# GEM_AVD_eFuse.net
KiCad netlist of a schematic drawn in Altium Designer
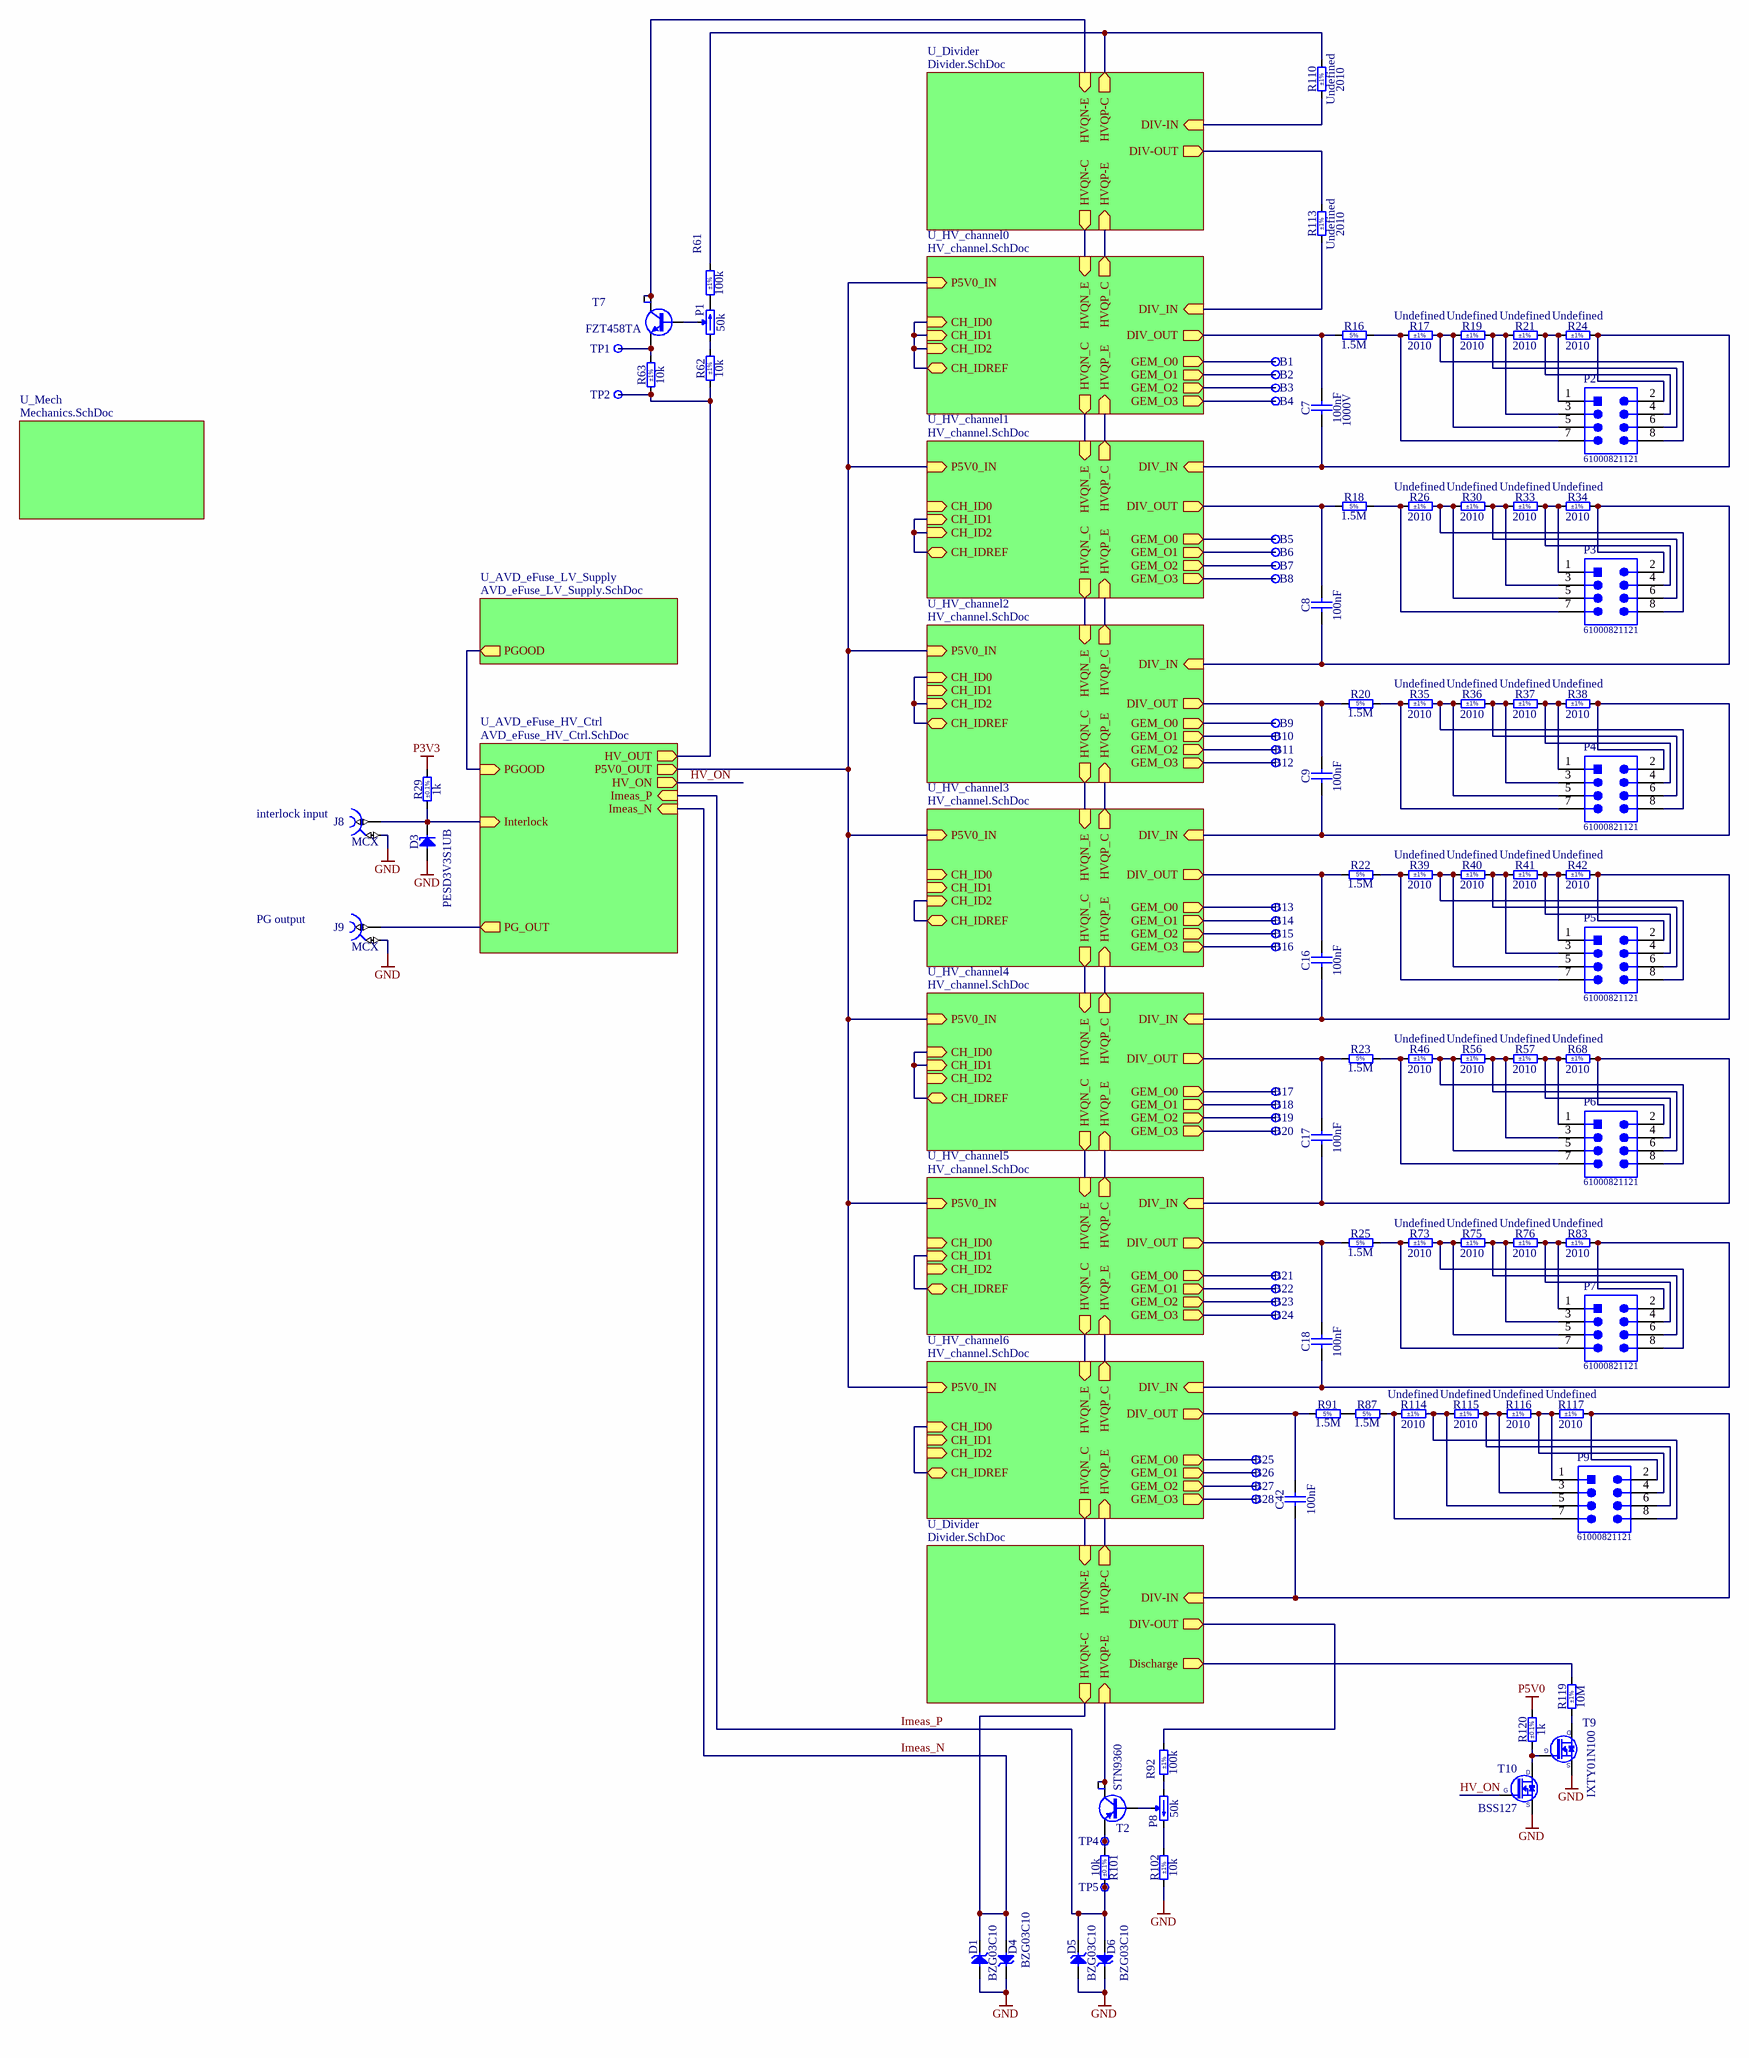
[diagram p0: GEM_AVD_eFuse.SchDoc]

(export (version "E")
  (design (tool "Eeschema 10.0.6"))
  (components
    (comp (ref "B1")
      (value "Socket")
      (footprint "MULTI-CONTACT_23.1000")
      (description "Single Terminal Socket")
      (fields
        (field (name "PART NUMBER") "MULTI-CONTACT_23.1000")
        (field (name "MANUFACTURER") "MULTI-CONTACT")
        (field (name "AUTHOR") "CERN DEM JLC")
      )
      (libsource (lib "Connectors") (part "Single Terminal Socket"))
    )
    (comp (ref "B2")
      (value "Socket")
      (footprint "MULTI-CONTACT_23.1000")
      (description "Single Terminal Socket")
      (fields
        (field (name "PART NUMBER") "MULTI-CONTACT_23.1000")
        (field (name "MANUFACTURER") "MULTI-CONTACT")
        (field (name "AUTHOR") "CERN DEM JLC")
      )
      (libsource (lib "Connectors") (part "Single Terminal Socket"))
    )
    (comp (ref "B3")
      (value "Socket")
      (footprint "MULTI-CONTACT_23.1000")
      (description "Single Terminal Socket")
      (fields
        (field (name "PART NUMBER") "MULTI-CONTACT_23.1000")
        (field (name "MANUFACTURER") "MULTI-CONTACT")
        (field (name "AUTHOR") "CERN DEM JLC")
      )
      (libsource (lib "Connectors") (part "Single Terminal Socket"))
    )
    (comp (ref "B4")
      (value "Socket")
      (footprint "MULTI-CONTACT_23.1000")
      (description "Single Terminal Socket")
      (fields
        (field (name "PART NUMBER") "MULTI-CONTACT_23.1000")
        (field (name "MANUFACTURER") "MULTI-CONTACT")
        (field (name "AUTHOR") "CERN DEM JLC")
      )
      (libsource (lib "Connectors") (part "Single Terminal Socket"))
    )
    (comp (ref "B5")
      (value "Socket")
      (footprint "MULTI-CONTACT_23.1000")
      (description "Single Terminal Socket")
      (fields
        (field (name "PART NUMBER") "MULTI-CONTACT_23.1000")
        (field (name "MANUFACTURER") "MULTI-CONTACT")
        (field (name "AUTHOR") "CERN DEM JLC")
      )
      (libsource (lib "Connectors") (part "Single Terminal Socket"))
    )
    (comp (ref "B6")
      (value "Socket")
      (footprint "MULTI-CONTACT_23.1000")
      (description "Single Terminal Socket")
      (fields
        (field (name "PART NUMBER") "MULTI-CONTACT_23.1000")
        (field (name "MANUFACTURER") "MULTI-CONTACT")
        (field (name "AUTHOR") "CERN DEM JLC")
      )
      (libsource (lib "Connectors") (part "Single Terminal Socket"))
    )
    (comp (ref "B7")
      (value "Socket")
      (footprint "MULTI-CONTACT_23.1000")
      (description "Single Terminal Socket")
      (fields
        (field (name "PART NUMBER") "MULTI-CONTACT_23.1000")
        (field (name "MANUFACTURER") "MULTI-CONTACT")
        (field (name "AUTHOR") "CERN DEM JLC")
      )
      (libsource (lib "Connectors") (part "Single Terminal Socket"))
    )
    (comp (ref "B8")
      (value "Socket")
      (footprint "MULTI-CONTACT_23.1000")
      (description "Single Terminal Socket")
      (fields
        (field (name "PART NUMBER") "MULTI-CONTACT_23.1000")
        (field (name "MANUFACTURER") "MULTI-CONTACT")
        (field (name "AUTHOR") "CERN DEM JLC")
      )
      (libsource (lib "Connectors") (part "Single Terminal Socket"))
    )
    (comp (ref "B9")
      (value "Socket")
      (footprint "MULTI-CONTACT_23.1000")
      (description "Single Terminal Socket")
      (fields
        (field (name "PART NUMBER") "MULTI-CONTACT_23.1000")
        (field (name "MANUFACTURER") "MULTI-CONTACT")
        (field (name "AUTHOR") "CERN DEM JLC")
      )
      (libsource (lib "Connectors") (part "Single Terminal Socket"))
    )
    (comp (ref "B10")
      (value "Socket")
      (footprint "MULTI-CONTACT_23.1000")
      (description "Single Terminal Socket")
      (fields
        (field (name "PART NUMBER") "MULTI-CONTACT_23.1000")
        (field (name "MANUFACTURER") "MULTI-CONTACT")
        (field (name "AUTHOR") "CERN DEM JLC")
      )
      (libsource (lib "Connectors") (part "Single Terminal Socket"))
    )
    (comp (ref "B11")
      (value "Socket")
      (footprint "MULTI-CONTACT_23.1000")
      (description "Single Terminal Socket")
      (fields
        (field (name "PART NUMBER") "MULTI-CONTACT_23.1000")
        (field (name "MANUFACTURER") "MULTI-CONTACT")
        (field (name "AUTHOR") "CERN DEM JLC")
      )
      (libsource (lib "Connectors") (part "Single Terminal Socket"))
    )
    (comp (ref "B12")
      (value "Socket")
      (footprint "MULTI-CONTACT_23.1000")
      (description "Single Terminal Socket")
      (fields
        (field (name "PART NUMBER") "MULTI-CONTACT_23.1000")
        (field (name "MANUFACTURER") "MULTI-CONTACT")
        (field (name "AUTHOR") "CERN DEM JLC")
      )
      (libsource (lib "Connectors") (part "Single Terminal Socket"))
    )
    (comp (ref "B13")
      (value "Socket")
      (footprint "MULTI-CONTACT_23.1000")
      (description "Single Terminal Socket")
      (fields
        (field (name "PART NUMBER") "MULTI-CONTACT_23.1000")
        (field (name "MANUFACTURER") "MULTI-CONTACT")
        (field (name "AUTHOR") "CERN DEM JLC")
      )
      (libsource (lib "Connectors") (part "Single Terminal Socket"))
    )
    (comp (ref "B14")
      (value "Socket")
      (footprint "MULTI-CONTACT_23.1000")
      (description "Single Terminal Socket")
      (fields
        (field (name "PART NUMBER") "MULTI-CONTACT_23.1000")
        (field (name "MANUFACTURER") "MULTI-CONTACT")
        (field (name "AUTHOR") "CERN DEM JLC")
      )
      (libsource (lib "Connectors") (part "Single Terminal Socket"))
    )
    (comp (ref "B15")
      (value "Socket")
      (footprint "MULTI-CONTACT_23.1000")
      (description "Single Terminal Socket")
      (fields
        (field (name "PART NUMBER") "MULTI-CONTACT_23.1000")
        (field (name "MANUFACTURER") "MULTI-CONTACT")
        (field (name "AUTHOR") "CERN DEM JLC")
      )
      (libsource (lib "Connectors") (part "Single Terminal Socket"))
    )
    (comp (ref "B16")
      (value "Socket")
      (footprint "MULTI-CONTACT_23.1000")
      (description "Single Terminal Socket")
      (fields
        (field (name "PART NUMBER") "MULTI-CONTACT_23.1000")
        (field (name "MANUFACTURER") "MULTI-CONTACT")
        (field (name "AUTHOR") "CERN DEM JLC")
      )
      (libsource (lib "Connectors") (part "Single Terminal Socket"))
    )
    (comp (ref "B17")
      (value "Socket")
      (footprint "MULTI-CONTACT_23.1000")
      (description "Single Terminal Socket")
      (fields
        (field (name "PART NUMBER") "MULTI-CONTACT_23.1000")
        (field (name "MANUFACTURER") "MULTI-CONTACT")
        (field (name "AUTHOR") "CERN DEM JLC")
      )
      (libsource (lib "Connectors") (part "Single Terminal Socket"))
    )
    (comp (ref "B18")
      (value "Socket")
      (footprint "MULTI-CONTACT_23.1000")
      (description "Single Terminal Socket")
      (fields
        (field (name "PART NUMBER") "MULTI-CONTACT_23.1000")
        (field (name "MANUFACTURER") "MULTI-CONTACT")
        (field (name "AUTHOR") "CERN DEM JLC")
      )
      (libsource (lib "Connectors") (part "Single Terminal Socket"))
    )
    (comp (ref "B19")
      (value "Socket")
      (footprint "MULTI-CONTACT_23.1000")
      (description "Single Terminal Socket")
      (fields
        (field (name "PART NUMBER") "MULTI-CONTACT_23.1000")
        (field (name "MANUFACTURER") "MULTI-CONTACT")
        (field (name "AUTHOR") "CERN DEM JLC")
      )
      (libsource (lib "Connectors") (part "Single Terminal Socket"))
    )
    (comp (ref "B20")
      (value "Socket")
      (footprint "MULTI-CONTACT_23.1000")
      (description "Single Terminal Socket")
      (fields
        (field (name "PART NUMBER") "MULTI-CONTACT_23.1000")
        (field (name "MANUFACTURER") "MULTI-CONTACT")
        (field (name "AUTHOR") "CERN DEM JLC")
      )
      (libsource (lib "Connectors") (part "Single Terminal Socket"))
    )
    (comp (ref "B21")
      (value "Socket")
      (footprint "MULTI-CONTACT_23.1000")
      (description "Single Terminal Socket")
      (fields
        (field (name "PART NUMBER") "MULTI-CONTACT_23.1000")
        (field (name "MANUFACTURER") "MULTI-CONTACT")
        (field (name "AUTHOR") "CERN DEM JLC")
      )
      (libsource (lib "Connectors") (part "Single Terminal Socket"))
    )
    (comp (ref "B22")
      (value "Socket")
      (footprint "MULTI-CONTACT_23.1000")
      (description "Single Terminal Socket")
      (fields
        (field (name "PART NUMBER") "MULTI-CONTACT_23.1000")
        (field (name "MANUFACTURER") "MULTI-CONTACT")
        (field (name "AUTHOR") "CERN DEM JLC")
      )
      (libsource (lib "Connectors") (part "Single Terminal Socket"))
    )
    (comp (ref "B23")
      (value "Socket")
      (footprint "MULTI-CONTACT_23.1000")
      (description "Single Terminal Socket")
      (fields
        (field (name "PART NUMBER") "MULTI-CONTACT_23.1000")
        (field (name "MANUFACTURER") "MULTI-CONTACT")
        (field (name "AUTHOR") "CERN DEM JLC")
      )
      (libsource (lib "Connectors") (part "Single Terminal Socket"))
    )
    (comp (ref "B24")
      (value "Socket")
      (footprint "MULTI-CONTACT_23.1000")
      (description "Single Terminal Socket")
      (fields
        (field (name "PART NUMBER") "MULTI-CONTACT_23.1000")
        (field (name "MANUFACTURER") "MULTI-CONTACT")
        (field (name "AUTHOR") "CERN DEM JLC")
      )
      (libsource (lib "Connectors") (part "Single Terminal Socket"))
    )
    (comp (ref "B25")
      (value "Socket")
      (footprint "MULTI-CONTACT_23.1000")
      (description "Single Terminal Socket")
      (fields
        (field (name "PART NUMBER") "MULTI-CONTACT_23.1000")
        (field (name "MANUFACTURER") "MULTI-CONTACT")
        (field (name "AUTHOR") "CERN DEM JLC")
      )
      (libsource (lib "Connectors") (part "Single Terminal Socket"))
    )
    (comp (ref "B26")
      (value "Socket")
      (footprint "MULTI-CONTACT_23.1000")
      (description "Single Terminal Socket")
      (fields
        (field (name "PART NUMBER") "MULTI-CONTACT_23.1000")
        (field (name "MANUFACTURER") "MULTI-CONTACT")
        (field (name "AUTHOR") "CERN DEM JLC")
      )
      (libsource (lib "Connectors") (part "Single Terminal Socket"))
    )
    (comp (ref "B27")
      (value "Socket")
      (footprint "MULTI-CONTACT_23.1000")
      (description "Single Terminal Socket")
      (fields
        (field (name "PART NUMBER") "MULTI-CONTACT_23.1000")
        (field (name "MANUFACTURER") "MULTI-CONTACT")
        (field (name "AUTHOR") "CERN DEM JLC")
      )
      (libsource (lib "Connectors") (part "Single Terminal Socket"))
    )
    (comp (ref "B28")
      (value "Socket")
      (footprint "MULTI-CONTACT_23.1000")
      (description "Single Terminal Socket")
      (fields
        (field (name "PART NUMBER") "MULTI-CONTACT_23.1000")
        (field (name "MANUFACTURER") "MULTI-CONTACT")
        (field (name "AUTHOR") "CERN DEM JLC")
      )
      (libsource (lib "Connectors") (part "Single Terminal Socket"))
    )
    (comp (ref "C7")
      (value "100nF")
      (footprint "CAPC4532X185N")
      (description "Non-polarised capacitor")
      (fields
        (field (name "PART NUMBER") "CC1812_100NF_1000V_10%_X7R_KEMET_HV FT-CAP")
        (field (name "VOLTAGE") "1000V")
        (field (name "TOLERANCE") "±10%")
        (field (name "AUTHOR") "CERN DEM MR")
      )
      (libsource (lib "Capacitors") (part "Capacitor - non polarized"))
    )
    (comp (ref "C8")
      (value "100nF")
      (footprint "CAPC4532X185N")
      (description "Non-polarised capacitor")
      (fields
        (field (name "PART NUMBER") "CC1812_100NF_1000V_10%_X7R_KEMET_HV FT-CAP")
        (field (name "VOLTAGE") "1000V")
        (field (name "AUTHOR") "CERN DEM MR")
      )
      (libsource (lib "Capacitors") (part "Capacitor - non polarized"))
    )
    (comp (ref "C9")
      (value "100nF")
      (footprint "CAPC4532X185N")
      (description "Non-polarised capacitor")
      (fields
        (field (name "PART NUMBER") "CC1812_100NF_1000V_10%_X7R_KEMET_HV FT-CAP")
        (field (name "VOLTAGE") "1000V")
        (field (name "AUTHOR") "CERN DEM MR")
      )
      (libsource (lib "Capacitors") (part "Capacitor - non polarized"))
    )
    (comp (ref "C16")
      (value "100nF")
      (footprint "CAPC4532X185N")
      (description "Non-polarised capacitor")
      (fields
        (field (name "PART NUMBER") "CC1812_100NF_1000V_10%_X7R_KEMET_HV FT-CAP")
        (field (name "VOLTAGE") "1000V")
        (field (name "AUTHOR") "CERN DEM MR")
      )
      (libsource (lib "Capacitors") (part "Capacitor - non polarized"))
    )
    (comp (ref "C17")
      (value "100nF")
      (footprint "CAPC4532X185N")
      (description "Non-polarised capacitor")
      (fields
        (field (name "PART NUMBER") "CC1812_100NF_1000V_10%_X7R_KEMET_HV FT-CAP")
        (field (name "VOLTAGE") "1000V")
        (field (name "AUTHOR") "CERN DEM MR")
      )
      (libsource (lib "Capacitors") (part "Capacitor - non polarized"))
    )
    (comp (ref "C18")
      (value "100nF")
      (footprint "CAPC4532X185N")
      (description "Non-polarised capacitor")
      (fields
        (field (name "PART NUMBER") "CC1812_100NF_1000V_10%_X7R_KEMET_HV FT-CAP")
        (field (name "VOLTAGE") "1000V")
        (field (name "AUTHOR") "CERN DEM MR")
      )
      (libsource (lib "Capacitors") (part "Capacitor - non polarized"))
    )
    (comp (ref "C42")
      (value "100nF")
      (footprint "CAPC4532X185N")
      (description "Non-polarised capacitor")
      (fields
        (field (name "PART NUMBER") "CC1812_100NF_1000V_10%_X7R_KEMET_HV FT-CAP")
        (field (name "VOLTAGE") "1000V")
        (field (name "AUTHOR") "CERN DEM MR")
      )
      (libsource (lib "Capacitors") (part "Capacitor - non polarized"))
    )
    (comp (ref "D1")
      (value "BZG03C10")
      (footprint "DIOM5326X230N")
      (description "Zener Diode")
      (fields
        (field (name "VOLTAGE") "10V")
        (field (name "POWER") "1.25W")
        (field (name "AUTHOR") "CERN DEM JLC")
      )
      (libsource (lib "ICs And Semiconductors") (part "Diode Zener"))
    )
    (comp (ref "D3")
      (value "PESD3V3S1UB")
      (footprint "SODFL1608X65N")
      (description "ESD protection diode")
      (fields
        (field (name "VOLTAGE") "3V3")
        (field (name "POWER") "330W")
        (field (name "AUTHOR") "CERN DEM JLC")
      )
      (libsource (lib "ICs And Semiconductors") (part "Diode ESD"))
    )
    (comp (ref "D4")
      (value "BZG03C10")
      (footprint "DIOM5326X230N")
      (description "Zener Diode")
      (fields
        (field (name "VOLTAGE") "10V")
        (field (name "POWER") "1.25W")
        (field (name "AUTHOR") "CERN DEM JLC")
      )
      (libsource (lib "ICs And Semiconductors") (part "Diode Zener"))
    )
    (comp (ref "D5")
      (value "BZG03C10")
      (footprint "DIOM5326X230N")
      (description "Zener Diode")
      (fields
        (field (name "VOLTAGE") "10V")
        (field (name "POWER") "1.25W")
        (field (name "AUTHOR") "CERN DEM JLC")
      )
      (libsource (lib "ICs And Semiconductors") (part "Diode Zener"))
    )
    (comp (ref "D6")
      (value "BZG03C10")
      (footprint "DIOM5326X230N")
      (description "Zener Diode")
      (fields
        (field (name "VOLTAGE") "10V")
        (field (name "POWER") "1.25W")
        (field (name "AUTHOR") "CERN DEM JLC")
      )
      (libsource (lib "ICs And Semiconductors") (part "Diode Zener"))
    )
    (comp (ref "J8")
      (value "MCX")
      (footprint "AMPHENOL_919-383J-51A")
      (fields
        (field (name "PART NUMBER") "AMPHENOL_919-383J-51A")
        (field (name "MANUFACTURER") "AMPHENOL")
        (field (name "MANUFACTURER PART NUMBER") "919-383J-51A")
        (field (name "AUTHOR") "CERN DEM BC")
      )
      (libsource (lib "Connectors") (part "Coax_1Female_1Shield"))
    )
    (comp (ref "J9")
      (value "MCX")
      (footprint "AMPHENOL_919-383J-51A")
      (fields
        (field (name "PART NUMBER") "AMPHENOL_919-383J-51A")
        (field (name "MANUFACTURER") "AMPHENOL")
        (field (name "MANUFACTURER PART NUMBER") "919-383J-51A")
        (field (name "AUTHOR") "CERN DEM BC")
      )
      (libsource (lib "Connectors") (part "Coax_1Female_1Shield"))
    )
    (comp (ref "P1")
      (value "50k")
      (footprint "TRIM_BOURNS_3266W")
      (description "Trimming Potentiometer")
      (fields
        (field (name "PART NUMBER") "TRIM_12T_50K_BOURNS_3266W-1-503LF")
        (field (name "POWER") "0.25W")
        (field (name "AUTHOR") "CERN DEM JMW")
      )
      (libsource (lib "Resistors") (part "Trimming Potentiometer"))
    )
    (comp (ref "P2")
      (value "61000821121")
      (footprint "61000821121")
      (description "WR-PHD Pin Header, SMT, pitch 2.54mm, Dual Row, Vertical, 8p")
      (fields (field (name "MANUFACTURER") "Wurth Elektronik"))
      (libsource (lib "Altium_WR-PHD (rev22a)") (part "61000821121"))
    )
    (comp (ref "P3")
      (value "61000821121")
      (footprint "61000821121")
      (description "WR-PHD Pin Header, SMT, pitch 2.54mm, Dual Row, Vertical, 8p")
      (fields (field (name "MANUFACTURER") "Wurth Elektronik"))
      (libsource (lib "Altium_WR-PHD (rev22a)") (part "61000821121"))
    )
    (comp (ref "P4")
      (value "61000821121")
      (footprint "61000821121")
      (description "WR-PHD Pin Header, SMT, pitch 2.54mm, Dual Row, Vertical, 8p")
      (fields (field (name "MANUFACTURER") "Wurth Elektronik"))
      (libsource (lib "Altium_WR-PHD (rev22a)") (part "61000821121"))
    )
    (comp (ref "P5")
      (value "61000821121")
      (footprint "61000821121")
      (description "WR-PHD Pin Header, SMT, pitch 2.54mm, Dual Row, Vertical, 8p")
      (fields (field (name "MANUFACTURER") "Wurth Elektronik"))
      (libsource (lib "Altium_WR-PHD (rev22a)") (part "61000821121"))
    )
    (comp (ref "P6")
      (value "61000821121")
      (footprint "61000821121")
      (description "WR-PHD Pin Header, SMT, pitch 2.54mm, Dual Row, Vertical, 8p")
      (fields (field (name "MANUFACTURER") "Wurth Elektronik"))
      (libsource (lib "Altium_WR-PHD (rev22a)") (part "61000821121"))
    )
    (comp (ref "P7")
      (value "61000821121")
      (footprint "61000821121")
      (description "WR-PHD Pin Header, SMT, pitch 2.54mm, Dual Row, Vertical, 8p")
      (fields (field (name "MANUFACTURER") "Wurth Elektronik"))
      (libsource (lib "Altium_WR-PHD (rev22a)") (part "61000821121"))
    )
    (comp (ref "P8")
      (value "50k")
      (footprint "TRIM_BOURNS_3266W")
      (description "Trimming Potentiometer")
      (fields
        (field (name "PART NUMBER") "TRIM_12T_50K_BOURNS_3266W-1-503LF")
        (field (name "POWER") "0.25W")
        (field (name "AUTHOR") "CERN DEM JMW")
      )
      (libsource (lib "Resistors") (part "Trimming Potentiometer"))
    )
    (comp (ref "P9")
      (value "61000821121")
      (footprint "61000821121")
      (description "WR-PHD Pin Header, SMT, pitch 2.54mm, Dual Row, Vertical, 8p")
      (fields (field (name "MANUFACTURER") "Wurth Elektronik"))
      (libsource (lib "Altium_WR-PHD (rev22a)") (part "61000821121"))
    )
    (comp (ref "R16")
      (value "1.5M")
      (footprint "RESC3225X70N")
      (description "Resistor - 5%")
      (fields
        (field (name "PART NUMBER") "R1210_1.5M_5%_0.5W_100PPM")
        (field (name "POWER") "0.5W")
        (field (name "AUTHOR") "CERN DEM HF")
      )
      (libsource (lib "Resistors") (part "Resistor - 5%"))
    )
    (comp (ref "R17")
      (value "Undefined")
      (footprint "RES_VISHAY_CRHV2010A")
      (description "Resistor - 1%")
      (fields
        (field (name "TOLERANCE") "±1%")
        (field (name "POWER") "0.5W")
        (field (name "MANUFACTURER") "VISHAY TECHNO")
        (field (name "CASE") "2010")
        (field (name "AUTHOR") "CERN DEM JLC")
      )
      (libsource (lib "Resistors") (part "Resistor - 1%"))
    )
    (comp (ref "R18")
      (value "1.5M")
      (footprint "RESC3225X70N")
      (description "Resistor - 5%")
      (fields
        (field (name "PART NUMBER") "R1210_1.5M_5%_0.5W_100PPM")
        (field (name "POWER") "0.5W")
        (field (name "AUTHOR") "CERN DEM HF")
      )
      (libsource (lib "Resistors") (part "Resistor - 5%"))
    )
    (comp (ref "R19")
      (value "Undefined")
      (footprint "RES_VISHAY_CRHV2010A")
      (description "Resistor - 1%")
      (fields
        (field (name "TOLERANCE") "±1%")
        (field (name "POWER") "0.5W")
        (field (name "MANUFACTURER") "VISHAY TECHNO")
        (field (name "CASE") "2010")
        (field (name "AUTHOR") "CERN DEM JLC")
      )
      (libsource (lib "Resistors") (part "Resistor - 1%"))
    )
    (comp (ref "R20")
      (value "1.5M")
      (footprint "RESC3225X70N")
      (description "Resistor - 5%")
      (fields
        (field (name "PART NUMBER") "R1210_1.5M_5%_0.5W_100PPM")
        (field (name "POWER") "0.5W")
        (field (name "AUTHOR") "CERN DEM HF")
      )
      (libsource (lib "Resistors") (part "Resistor - 5%"))
    )
    (comp (ref "R21")
      (value "Undefined")
      (footprint "RES_VISHAY_CRHV2010A")
      (description "Resistor - 1%")
      (fields
        (field (name "TOLERANCE") "±1%")
        (field (name "POWER") "0.5W")
        (field (name "MANUFACTURER") "VISHAY TECHNO")
        (field (name "CASE") "2010")
        (field (name "AUTHOR") "CERN DEM JLC")
      )
      (libsource (lib "Resistors") (part "Resistor - 1%"))
    )
    (comp (ref "R22")
      (value "1.5M")
      (footprint "RESC3225X70N")
      (description "Resistor - 5%")
      (fields
        (field (name "PART NUMBER") "R1210_1.5M_5%_0.5W_100PPM")
        (field (name "POWER") "0.5W")
        (field (name "AUTHOR") "CERN DEM HF")
      )
      (libsource (lib "Resistors") (part "Resistor - 5%"))
    )
    (comp (ref "R23")
      (value "1.5M")
      (footprint "RESC3225X70N")
      (description "Resistor - 5%")
      (fields
        (field (name "PART NUMBER") "R1210_1.5M_5%_0.5W_100PPM")
        (field (name "POWER") "0.5W")
        (field (name "AUTHOR") "CERN DEM HF")
      )
      (libsource (lib "Resistors") (part "Resistor - 5%"))
    )
    (comp (ref "R24")
      (value "Undefined")
      (footprint "RES_VISHAY_CRHV2010A")
      (description "Resistor - 1%")
      (fields
        (field (name "TOLERANCE") "±1%")
        (field (name "POWER") "0.5W")
        (field (name "MANUFACTURER") "VISHAY TECHNO")
        (field (name "CASE") "2010")
        (field (name "AUTHOR") "CERN DEM JLC")
      )
      (libsource (lib "Resistors") (part "Resistor - 1%"))
    )
    (comp (ref "R25")
      (value "1.5M")
      (footprint "RESC3225X70N")
      (description "Resistor - 5%")
      (fields
        (field (name "PART NUMBER") "R1210_1.5M_5%_0.5W_100PPM")
        (field (name "POWER") "0.5W")
        (field (name "AUTHOR") "CERN DEM HF")
      )
      (libsource (lib "Resistors") (part "Resistor - 5%"))
    )
    (comp (ref "R26")
      (value "Undefined")
      (footprint "RES_VISHAY_CRHV2010A")
      (description "Resistor - 1%")
      (fields
        (field (name "TOLERANCE") "±1%")
        (field (name "POWER") "0.5W")
        (field (name "MANUFACTURER") "VISHAY TECHNO")
        (field (name "CASE") "2010")
        (field (name "AUTHOR") "CERN DEM JLC")
      )
      (libsource (lib "Resistors") (part "Resistor - 1%"))
    )
    (comp (ref "R29")
      (value "1k")
      (footprint "RESC1608X55N")
      (description "Resistor - 0.1%")
      (fields
        (field (name "TOLERANCE") "±0.1%")
        (field (name "PART NUMBER") "R0603_1K_0.1%_0.063W_10PPM")
        (field (name "POWER") "0.063W")
        (field (name "AUTHOR") "CERN DEM BC")
      )
      (libsource (lib "Resistors") (part "Resistor - 0.1%"))
    )
    (comp (ref "R30")
      (value "Undefined")
      (footprint "RES_VISHAY_CRHV2010A")
      (description "Resistor - 1%")
      (fields
        (field (name "TOLERANCE") "±1%")
        (field (name "POWER") "0.5W")
        (field (name "MANUFACTURER") "VISHAY TECHNO")
        (field (name "CASE") "2010")
        (field (name "AUTHOR") "CERN DEM JLC")
      )
      (libsource (lib "Resistors") (part "Resistor - 1%"))
    )
    (comp (ref "R33")
      (value "Undefined")
      (footprint "RES_VISHAY_CRHV2010A")
      (description "Resistor - 1%")
      (fields
        (field (name "TOLERANCE") "±1%")
        (field (name "POWER") "0.5W")
        (field (name "MANUFACTURER") "VISHAY TECHNO")
        (field (name "CASE") "2010")
        (field (name "AUTHOR") "CERN DEM JLC")
      )
      (libsource (lib "Resistors") (part "Resistor - 1%"))
    )
    (comp (ref "R34")
      (value "Undefined")
      (footprint "RES_VISHAY_CRHV2010A")
      (description "Resistor - 1%")
      (fields
        (field (name "TOLERANCE") "±1%")
        (field (name "POWER") "0.5W")
        (field (name "MANUFACTURER") "VISHAY TECHNO")
        (field (name "CASE") "2010")
        (field (name "AUTHOR") "CERN DEM JLC")
      )
      (libsource (lib "Resistors") (part "Resistor - 1%"))
    )
    (comp (ref "R35")
      (value "Undefined")
      (footprint "RES_VISHAY_CRHV2010A")
      (description "Resistor - 1%")
      (fields
        (field (name "TOLERANCE") "±1%")
        (field (name "POWER") "0.5W")
        (field (name "MANUFACTURER") "VISHAY TECHNO")
        (field (name "CASE") "2010")
        (field (name "AUTHOR") "CERN DEM JLC")
      )
      (libsource (lib "Resistors") (part "Resistor - 1%"))
    )
    (comp (ref "R36")
      (value "Undefined")
      (footprint "RES_VISHAY_CRHV2010A")
      (description "Resistor - 1%")
      (fields
        (field (name "TOLERANCE") "±1%")
        (field (name "POWER") "0.5W")
        (field (name "MANUFACTURER") "VISHAY TECHNO")
        (field (name "CASE") "2010")
        (field (name "AUTHOR") "CERN DEM JLC")
      )
      (libsource (lib "Resistors") (part "Resistor - 1%"))
    )
    (comp (ref "R37")
      (value "Undefined")
      (footprint "RES_VISHAY_CRHV2010A")
      (description "Resistor - 1%")
      (fields
        (field (name "TOLERANCE") "±1%")
        (field (name "POWER") "0.5W")
        (field (name "MANUFACTURER") "VISHAY TECHNO")
        (field (name "CASE") "2010")
        (field (name "AUTHOR") "CERN DEM JLC")
      )
      (libsource (lib "Resistors") (part "Resistor - 1%"))
    )
    (comp (ref "R38")
      (value "Undefined")
      (footprint "RES_VISHAY_CRHV2010A")
      (description "Resistor - 1%")
      (fields
        (field (name "TOLERANCE") "±1%")
        (field (name "POWER") "0.5W")
        (field (name "MANUFACTURER") "VISHAY TECHNO")
        (field (name "CASE") "2010")
        (field (name "AUTHOR") "CERN DEM JLC")
      )
      (libsource (lib "Resistors") (part "Resistor - 1%"))
    )
    (comp (ref "R39")
      (value "Undefined")
      (footprint "RES_VISHAY_CRHV2010A")
      (description "Resistor - 1%")
      (fields
        (field (name "TOLERANCE") "±1%")
        (field (name "POWER") "0.5W")
        (field (name "MANUFACTURER") "VISHAY TECHNO")
        (field (name "CASE") "2010")
        (field (name "AUTHOR") "CERN DEM JLC")
      )
      (libsource (lib "Resistors") (part "Resistor - 1%"))
    )
    (comp (ref "R40")
      (value "Undefined")
      (footprint "RES_VISHAY_CRHV2010A")
      (description "Resistor - 1%")
      (fields
        (field (name "TOLERANCE") "±1%")
        (field (name "POWER") "0.5W")
        (field (name "MANUFACTURER") "VISHAY TECHNO")
        (field (name "CASE") "2010")
        (field (name "AUTHOR") "CERN DEM JLC")
      )
      (libsource (lib "Resistors") (part "Resistor - 1%"))
    )
    (comp (ref "R41")
      (value "Undefined")
      (footprint "RES_VISHAY_CRHV2010A")
      (description "Resistor - 1%")
      (fields
        (field (name "TOLERANCE") "±1%")
        (field (name "POWER") "0.5W")
        (field (name "MANUFACTURER") "VISHAY TECHNO")
        (field (name "CASE") "2010")
        (field (name "AUTHOR") "CERN DEM JLC")
      )
      (libsource (lib "Resistors") (part "Resistor - 1%"))
    )
    (comp (ref "R42")
      (value "Undefined")
      (footprint "RES_VISHAY_CRHV2010A")
      (description "Resistor - 1%")
      (fields
        (field (name "TOLERANCE") "±1%")
        (field (name "POWER") "0.5W")
        (field (name "MANUFACTURER") "VISHAY TECHNO")
        (field (name "CASE") "2010")
        (field (name "AUTHOR") "CERN DEM JLC")
      )
      (libsource (lib "Resistors") (part "Resistor - 1%"))
    )
    (comp (ref "R46")
      (value "Undefined")
      (footprint "RES_VISHAY_CRHV2010A")
      (description "Resistor - 1%")
      (fields
        (field (name "TOLERANCE") "±1%")
        (field (name "POWER") "0.5W")
        (field (name "MANUFACTURER") "VISHAY TECHNO")
        (field (name "CASE") "2010")
        (field (name "AUTHOR") "CERN DEM JLC")
      )
      (libsource (lib "Resistors") (part "Resistor - 1%"))
    )
    (comp (ref "R56")
      (value "Undefined")
      (footprint "RES_VISHAY_CRHV2010A")
      (description "Resistor - 1%")
      (fields
        (field (name "TOLERANCE") "±1%")
        (field (name "POWER") "0.5W")
        (field (name "MANUFACTURER") "VISHAY TECHNO")
        (field (name "CASE") "2010")
        (field (name "AUTHOR") "CERN DEM JLC")
      )
      (libsource (lib "Resistors") (part "Resistor - 1%"))
    )
    (comp (ref "R57")
      (value "Undefined")
      (footprint "RES_VISHAY_CRHV2010A")
      (description "Resistor - 1%")
      (fields
        (field (name "TOLERANCE") "±1%")
        (field (name "POWER") "0.5W")
        (field (name "MANUFACTURER") "VISHAY TECHNO")
        (field (name "CASE") "2010")
        (field (name "AUTHOR") "CERN DEM JLC")
      )
      (libsource (lib "Resistors") (part "Resistor - 1%"))
    )
    (comp (ref "R61")
      (value "100k")
      (footprint "RESC6331X70N")
      (description "Resistor - 1%")
      (fields
        (field (name "TOLERANCE") "±1%")
        (field (name "PART NUMBER") "R2512_100K_1%_1W_100PPM")
        (field (name "POWER") "1W")
        (field (name "AUTHOR") "CERN DEM JLC")
      )
      (libsource (lib "Resistors") (part "Resistor - 1%"))
    )
    (comp (ref "R62")
      (value "10k")
      (footprint "RESC3216X65N")
      (description "Resistor - 1%")
      (fields
        (field (name "TOLERANCE") "±1%")
        (field (name "PART NUMBER") "R1206_10K_1%_0.25W_100PPM")
        (field (name "POWER") "0.25W")
        (field (name "AUTHOR") "CERN DEM JLC")
      )
      (libsource (lib "Resistors") (part "Resistor - 1%"))
    )
    (comp (ref "R63")
      (value "10k")
      (footprint "RESC3216X65N")
      (description "Resistor - 1%")
      (fields
        (field (name "TOLERANCE") "±1%")
        (field (name "PART NUMBER") "R1206_10K_1%_0.25W_100PPM")
        (field (name "POWER") "0.25W")
        (field (name "AUTHOR") "CERN DEM JLC")
      )
      (libsource (lib "Resistors") (part "Resistor - 1%"))
    )
    (comp (ref "R68")
      (value "Undefined")
      (footprint "RES_VISHAY_CRHV2010A")
      (description "Resistor - 1%")
      (fields
        (field (name "TOLERANCE") "±1%")
        (field (name "POWER") "0.5W")
        (field (name "MANUFACTURER") "VISHAY TECHNO")
        (field (name "CASE") "2010")
        (field (name "AUTHOR") "CERN DEM JLC")
      )
      (libsource (lib "Resistors") (part "Resistor - 1%"))
    )
    (comp (ref "R73")
      (value "Undefined")
      (footprint "RES_VISHAY_CRHV2010A")
      (description "Resistor - 1%")
      (fields
        (field (name "TOLERANCE") "±1%")
        (field (name "POWER") "0.5W")
        (field (name "MANUFACTURER") "VISHAY TECHNO")
        (field (name "CASE") "2010")
        (field (name "AUTHOR") "CERN DEM JLC")
      )
      (libsource (lib "Resistors") (part "Resistor - 1%"))
    )
    (comp (ref "R75")
      (value "Undefined")
      (footprint "RES_VISHAY_CRHV2010A")
      (description "Resistor - 1%")
      (fields
        (field (name "TOLERANCE") "±1%")
        (field (name "POWER") "0.5W")
        (field (name "MANUFACTURER") "VISHAY TECHNO")
        (field (name "CASE") "2010")
        (field (name "AUTHOR") "CERN DEM JLC")
      )
      (libsource (lib "Resistors") (part "Resistor - 1%"))
    )
    (comp (ref "R76")
      (value "Undefined")
      (footprint "RES_VISHAY_CRHV2010A")
      (description "Resistor - 1%")
      (fields
        (field (name "TOLERANCE") "±1%")
        (field (name "POWER") "0.5W")
        (field (name "MANUFACTURER") "VISHAY TECHNO")
        (field (name "CASE") "2010")
        (field (name "AUTHOR") "CERN DEM JLC")
      )
      (libsource (lib "Resistors") (part "Resistor - 1%"))
    )
    (comp (ref "R83")
      (value "Undefined")
      (footprint "RES_VISHAY_CRHV2010A")
      (description "Resistor - 1%")
      (fields
        (field (name "TOLERANCE") "±1%")
        (field (name "POWER") "0.5W")
        (field (name "MANUFACTURER") "VISHAY TECHNO")
        (field (name "CASE") "2010")
        (field (name "AUTHOR") "CERN DEM JLC")
      )
      (libsource (lib "Resistors") (part "Resistor - 1%"))
    )
    (comp (ref "R87")
      (value "1.5M")
      (footprint "RESC3225X70N")
      (description "Resistor - 5%")
      (fields
        (field (name "PART NUMBER") "R1210_1.5M_5%_0.5W_100PPM")
        (field (name "POWER") "0.5W")
        (field (name "AUTHOR") "CERN DEM HF")
      )
      (libsource (lib "Resistors") (part "Resistor - 5%"))
    )
    (comp (ref "R91")
      (value "1.5M")
      (footprint "RESC3225X70N")
      (description "Resistor - 5%")
      (fields
        (field (name "PART NUMBER") "R1210_1.5M_5%_0.5W_100PPM")
        (field (name "POWER") "0.5W")
        (field (name "AUTHOR") "CERN DEM HF")
      )
      (libsource (lib "Resistors") (part "Resistor - 5%"))
    )
    (comp (ref "R92")
      (value "100k")
      (footprint "RESC6331X70N")
      (description "Resistor - 1%")
      (fields
        (field (name "TOLERANCE") "±1%")
        (field (name "PART NUMBER") "R2512_100K_1%_1W_100PPM")
        (field (name "POWER") "1W")
        (field (name "AUTHOR") "CERN DEM JLC")
      )
      (libsource (lib "Resistors") (part "Resistor - 1%"))
    )
    (comp (ref "R101")
      (value "10k")
      (footprint "RESC1608X64N")
      (description "Resistor - 0.1%")
      (fields
        (field (name "TOLERANCE") "±0.1%")
        (field (name "PART NUMBER") "R0603_10K_0.1%_0.1W_25PPM")
        (field (name "POWER") "0.1W")
        (field (name "AUTHOR") "CERN DEM JMW")
      )
      (libsource (lib "Resistors") (part "Resistor - 0.1%"))
    )
    (comp (ref "R102")
      (value "10k")
      (footprint "RESC3216X65N")
      (description "Resistor - 1%")
      (fields
        (field (name "TOLERANCE") "±1%")
        (field (name "PART NUMBER") "R1206_10K_1%_0.25W_100PPM")
        (field (name "POWER") "0.25W")
        (field (name "AUTHOR") "CERN DEM JLC")
      )
      (libsource (lib "Resistors") (part "Resistor - 1%"))
    )
    (comp (ref "R110")
      (value "Undefined")
      (footprint "RES_VISHAY_CRHV2010A")
      (description "Resistor - 1%")
      (fields
        (field (name "TOLERANCE") "±1%")
        (field (name "POWER") "0.5W")
        (field (name "MANUFACTURER") "VISHAY TECHNO")
        (field (name "CASE") "2010")
        (field (name "AUTHOR") "CERN DEM JLC")
      )
      (libsource (lib "Resistors") (part "Resistor - 1%"))
    )
    (comp (ref "R113")
      (value "Undefined")
      (footprint "RES_VISHAY_CRHV2010A")
      (description "Resistor - 1%")
      (fields
        (field (name "TOLERANCE") "±1%")
        (field (name "POWER") "0.5W")
        (field (name "MANUFACTURER") "VISHAY TECHNO")
        (field (name "CASE") "2010")
        (field (name "AUTHOR") "CERN DEM JLC")
      )
      (libsource (lib "Resistors") (part "Resistor - 1%"))
    )
    (comp (ref "R114")
      (value "Undefined")
      (footprint "RES_VISHAY_CRHV2010A")
      (description "Resistor - 1%")
      (fields
        (field (name "TOLERANCE") "±1%")
        (field (name "POWER") "0.5W")
        (field (name "MANUFACTURER") "VISHAY TECHNO")
        (field (name "CASE") "2010")
        (field (name "AUTHOR") "CERN DEM JLC")
      )
      (libsource (lib "Resistors") (part "Resistor - 1%"))
    )
    (comp (ref "R115")
      (value "Undefined")
      (footprint "RES_VISHAY_CRHV2010A")
      (description "Resistor - 1%")
      (fields
        (field (name "TOLERANCE") "±1%")
        (field (name "POWER") "0.5W")
        (field (name "MANUFACTURER") "VISHAY TECHNO")
        (field (name "CASE") "2010")
        (field (name "AUTHOR") "CERN DEM JLC")
      )
      (libsource (lib "Resistors") (part "Resistor - 1%"))
    )
    (comp (ref "R116")
      (value "Undefined")
      (footprint "RES_VISHAY_CRHV2010A")
      (description "Resistor - 1%")
      (fields
        (field (name "TOLERANCE") "±1%")
        (field (name "POWER") "0.5W")
        (field (name "MANUFACTURER") "VISHAY TECHNO")
        (field (name "CASE") "2010")
        (field (name "AUTHOR") "CERN DEM JLC")
      )
      (libsource (lib "Resistors") (part "Resistor - 1%"))
    )
    (comp (ref "R117")
      (value "Undefined")
      (footprint "RES_VISHAY_CRHV2010A")
      (description "Resistor - 1%")
      (fields
        (field (name "TOLERANCE") "±1%")
        (field (name "POWER") "0.5W")
        (field (name "MANUFACTURER") "VISHAY TECHNO")
        (field (name "CASE") "2010")
        (field (name "AUTHOR") "CERN DEM JLC")
      )
      (libsource (lib "Resistors") (part "Resistor - 1%"))
    )
    (comp (ref "R119")
      (value "10M")
      (footprint "RESC5025X65N")
      (description "Resistor - 1%")
      (fields
        (field (name "TOLERANCE") "±1%")
        (field (name "PART NUMBER") "R2010_10M_1%_0.5W_200PPM")
        (field (name "POWER") "0.5W")
        (field (name "AUTHOR") "CERN DEM JLC")
      )
      (libsource (lib "Resistors") (part "Resistor - 1%"))
    )
    (comp (ref "R120")
      (value "1k")
      (footprint "RESC1608X55N")
      (description "Resistor - 0.1%")
      (fields
        (field (name "TOLERANCE") "±0.1%")
        (field (name "PART NUMBER") "R0603_1K_0.1%_0.063W_10PPM")
        (field (name "POWER") "0.063W")
        (field (name "AUTHOR") "CERN DEM BC")
      )
      (libsource (lib "Resistors") (part "Resistor - 0.1%"))
    )
    (comp (ref "T2")
      (value "STN9360")
      (footprint "SOT230P700X180-4N")
      (description "PNP Transistor")
      (fields (field (name "MANUFACTURER") "STMicroelectronics") (field (name "AUTHOR") "FS"))
      (libsource (lib "templib") (part "STN9360"))
    )
    (comp (ref "T7")
      (value "FZT458TA")
      (footprint "SOT230P700X180-4N")
      (description "NPN Transistor")
      (fields (field (name "MANUFACTURER") "DIODES INCORPORATED") (field (name "AUTHOR") "CERN DEM JLC"))
      (libsource (lib "ICs And Semiconductors") (part "NPN B1 C2 E3 C4"))
    )
    (comp (ref "T9")
      (value "IXTY01N100")
      (footprint "TO228P991X238-3N-R648X546")
      (description "N-CHANNEL MOSFET WITH DIODE")
      (fields (field (name "MANUFACTURER") "IXYS") (field (name "AUTHOR") "CERN DEM JLC"))
      (libsource (lib "") (part "N-MOSFET-D 1G 2S 3D_1"))
    )
    (comp (ref "T10")
      (value "BSS127")
      (footprint "SOT95P240X110-3N")
      (description "N-CHANNEL MOSFET WITH DIODE")
      (fields (field (name "MANUFACTURER") "INFINEON") (field (name "AUTHOR") "CERN DEM HF"))
      (libsource (lib "ICs And Semiconductors") (part "N-MOSFET-D 1G 2S 3D"))
    )
    (comp (ref "TP1")
      (value "Test Point")
      (footprint "TPS127")
      (fields (field (name "PART NUMBER") "SMD_PAD_1.27X1.27MM") (field (name "AUTHOR") "CERN DEM JLC"))
      (libsource (lib "Eletro-mechanical") (part "Test Point"))
    )
    (comp (ref "TP2")
      (value "Test Point")
      (footprint "TPS127")
      (fields (field (name "PART NUMBER") "SMD_PAD_1.27X1.27MM") (field (name "AUTHOR") "CERN DEM JLC"))
      (libsource (lib "Eletro-mechanical") (part "Test Point"))
    )
    (comp (ref "TP4")
      (value "Test Point")
      (footprint "TPS127")
      (fields (field (name "PART NUMBER") "SMD_PAD_1.27X1.27MM") (field (name "AUTHOR") "CERN DEM JLC"))
      (libsource (lib "Eletro-mechanical") (part "Test Point"))
    )
    (comp (ref "TP5")
      (value "Test Point")
      (footprint "TPS127")
      (fields (field (name "PART NUMBER") "SMD_PAD_1.27X1.27MM") (field (name "AUTHOR") "CERN DEM JLC"))
      (libsource (lib "Eletro-mechanical") (part "Test Point"))
    )
  )
  (nets
    (net (code "17") (name "/DIV-IN") (class "Default")
      (node (ref "R110") (pin "1") (pinfunction "1_1") (pintype "passive"))
    )
    (net (code "18") (name "/DIV-IN_1") (class "Default")
      (node (ref "C42") (pin "1") (pinfunction "1_1") (pintype "passive"))
      (node (ref "P9") (pin "2") (pinfunction "2_2") (pintype "passive"))
      (node (ref "R117") (pin "2") (pinfunction "2_2") (pintype "passive"))
    )
    (net (code "19") (name "/DIV-OUT") (class "Default")
      (node (ref "R113") (pin "2") (pinfunction "2_2") (pintype "passive"))
    )
    (net (code "20") (name "/DIV-OUT_1") (class "Default")
      (node (ref "R92") (pin "1") (pinfunction "1_1") (pintype "passive"))
    )
    (net (code "21") (name "/DIV_IN") (class "Default")
      (node (ref "R113") (pin "1") (pinfunction "1_1") (pintype "passive"))
    )
    (net (code "22") (name "/DIV_IN_1") (class "Default")
      (node (ref "C18") (pin "1") (pinfunction "1_1") (pintype "passive"))
      (node (ref "P7") (pin "2") (pinfunction "2_2") (pintype "passive"))
      (node (ref "R83") (pin "2") (pinfunction "2_2") (pintype "passive"))
    )
    (net (code "23") (name "/DIV_IN_2") (class "Default")
      (node (ref "C16") (pin "1") (pinfunction "1_1") (pintype "passive"))
      (node (ref "P5") (pin "2") (pinfunction "2_2") (pintype "passive"))
      (node (ref "R42") (pin "2") (pinfunction "2_2") (pintype "passive"))
    )
    (net (code "24") (name "/DIV_IN_3") (class "Default")
      (node (ref "C17") (pin "1") (pinfunction "1_1") (pintype "passive"))
      (node (ref "P6") (pin "2") (pinfunction "2_2") (pintype "passive"))
      (node (ref "R68") (pin "2") (pinfunction "2_2") (pintype "passive"))
    )
    (net (code "25") (name "/DIV_IN_4") (class "Default")
      (node (ref "C9") (pin "1") (pinfunction "1_1") (pintype "passive"))
      (node (ref "P4") (pin "2") (pinfunction "2_2") (pintype "passive"))
      (node (ref "R38") (pin "2") (pinfunction "2_2") (pintype "passive"))
    )
    (net (code "26") (name "/DIV_IN_5") (class "Default")
      (node (ref "C7") (pin "1") (pinfunction "1_1") (pintype "passive"))
      (node (ref "P2") (pin "2") (pinfunction "2_2") (pintype "passive"))
      (node (ref "R24") (pin "2") (pinfunction "2_2") (pintype "passive"))
    )
    (net (code "27") (name "/DIV_IN_6") (class "Default")
      (node (ref "C8") (pin "1") (pinfunction "1_1") (pintype "passive"))
      (node (ref "P3") (pin "2") (pinfunction "2_2") (pintype "passive"))
      (node (ref "R34") (pin "2") (pinfunction "2_2") (pintype "passive"))
    )
    (net (code "28") (name "/DIV_OUT") (class "Default")
      (node (ref "C7") (pin "2") (pinfunction "2_2") (pintype "passive"))
      (node (ref "R16") (pin "1") (pinfunction "1_1") (pintype "passive"))
    )
    (net (code "29") (name "/DIV_OUT_1") (class "Default")
      (node (ref "C42") (pin "2") (pinfunction "2_2") (pintype "passive"))
      (node (ref "R91") (pin "1") (pinfunction "1_1") (pintype "passive"))
    )
    (net (code "30") (name "/DIV_OUT_2") (class "Default")
      (node (ref "C17") (pin "2") (pinfunction "2_2") (pintype "passive"))
      (node (ref "R23") (pin "1") (pinfunction "1_1") (pintype "passive"))
    )
    (net (code "31") (name "/DIV_OUT_3") (class "Default")
      (node (ref "C18") (pin "2") (pinfunction "2_2") (pintype "passive"))
      (node (ref "R25") (pin "1") (pinfunction "1_1") (pintype "passive"))
    )
    (net (code "32") (name "/DIV_OUT_4") (class "Default")
      (node (ref "C16") (pin "2") (pinfunction "2_2") (pintype "passive"))
      (node (ref "R22") (pin "1") (pinfunction "1_1") (pintype "passive"))
    )
    (net (code "33") (name "/DIV_OUT_5") (class "Default")
      (node (ref "C8") (pin "2") (pinfunction "2_2") (pintype "passive"))
      (node (ref "R18") (pin "1") (pinfunction "1_1") (pintype "passive"))
    )
    (net (code "34") (name "/DIV_OUT_6") (class "Default")
      (node (ref "C9") (pin "2") (pinfunction "2_2") (pintype "passive"))
      (node (ref "R20") (pin "1") (pinfunction "1_1") (pintype "passive"))
    )
    (net (code "35") (name "/Discharge") (class "Default")
      (node (ref "R119") (pin "2") (pinfunction "2_2") (pintype "passive"))
    )
    (net (code "36") (name "/GEM_O0") (class "Default")
      (node (ref "B9") (pin "1") (pinfunction "1_1") (pintype "bidirectional"))
    )
    (net (code "37") (name "/GEM_O0_1") (class "Default")
      (node (ref "B25") (pin "1") (pinfunction "1_1") (pintype "bidirectional"))
    )
    (net (code "38") (name "/GEM_O0_2") (class "Default")
      (node (ref "B17") (pin "1") (pinfunction "1_1") (pintype "bidirectional"))
    )
    (net (code "39") (name "/GEM_O0_3") (class "Default")
      (node (ref "B21") (pin "1") (pinfunction "1_1") (pintype "bidirectional"))
    )
    (net (code "40") (name "/GEM_O0_4") (class "Default")
      (node (ref "B13") (pin "1") (pinfunction "1_1") (pintype "bidirectional"))
    )
    (net (code "41") (name "/GEM_O0_5") (class "Default")
      (node (ref "B5") (pin "1") (pinfunction "1_1") (pintype "bidirectional"))
    )
    (net (code "42") (name "/GEM_O0_6") (class "Default")
      (node (ref "B1") (pin "1") (pinfunction "1_1") (pintype "bidirectional"))
    )
    (net (code "43") (name "/GEM_O1") (class "Default")
      (node (ref "B10") (pin "1") (pinfunction "1_1") (pintype "bidirectional"))
    )
    (net (code "44") (name "/GEM_O1_1") (class "Default")
      (node (ref "B26") (pin "1") (pinfunction "1_1") (pintype "bidirectional"))
    )
    (net (code "45") (name "/GEM_O1_2") (class "Default")
      (node (ref "B18") (pin "1") (pinfunction "1_1") (pintype "bidirectional"))
    )
    (net (code "46") (name "/GEM_O1_3") (class "Default")
      (node (ref "B22") (pin "1") (pinfunction "1_1") (pintype "bidirectional"))
    )
    (net (code "47") (name "/GEM_O1_4") (class "Default")
      (node (ref "B14") (pin "1") (pinfunction "1_1") (pintype "bidirectional"))
    )
    (net (code "48") (name "/GEM_O1_5") (class "Default")
      (node (ref "B6") (pin "1") (pinfunction "1_1") (pintype "bidirectional"))
    )
    (net (code "49") (name "/GEM_O1_6") (class "Default")
      (node (ref "B2") (pin "1") (pinfunction "1_1") (pintype "bidirectional"))
    )
    (net (code "50") (name "/GEM_O2") (class "Default")
      (node (ref "B11") (pin "1") (pinfunction "1_1") (pintype "bidirectional"))
    )
    (net (code "51") (name "/GEM_O2_1") (class "Default")
      (node (ref "B27") (pin "1") (pinfunction "1_1") (pintype "bidirectional"))
    )
    (net (code "52") (name "/GEM_O2_2") (class "Default")
      (node (ref "B19") (pin "1") (pinfunction "1_1") (pintype "bidirectional"))
    )
    (net (code "53") (name "/GEM_O2_3") (class "Default")
      (node (ref "B23") (pin "1") (pinfunction "1_1") (pintype "bidirectional"))
    )
    (net (code "54") (name "/GEM_O2_4") (class "Default")
      (node (ref "B15") (pin "1") (pinfunction "1_1") (pintype "bidirectional"))
    )
    (net (code "55") (name "/GEM_O2_5") (class "Default")
      (node (ref "B3") (pin "1") (pinfunction "1_1") (pintype "bidirectional"))
    )
    (net (code "56") (name "/GEM_O2_6") (class "Default")
      (node (ref "B7") (pin "1") (pinfunction "1_1") (pintype "bidirectional"))
    )
    (net (code "57") (name "/GEM_O3") (class "Default")
      (node (ref "B12") (pin "1") (pinfunction "1_1") (pintype "bidirectional"))
    )
    (net (code "58") (name "/GEM_O3_1") (class "Default")
      (node (ref "B28") (pin "1") (pinfunction "1_1") (pintype "bidirectional"))
    )
    (net (code "59") (name "/GEM_O3_2") (class "Default")
      (node (ref "B20") (pin "1") (pinfunction "1_1") (pintype "bidirectional"))
    )
    (net (code "60") (name "/GEM_O3_3") (class "Default")
      (node (ref "B24") (pin "1") (pinfunction "1_1") (pintype "bidirectional"))
    )
    (net (code "61") (name "/GEM_O3_4") (class "Default")
      (node (ref "B16") (pin "1") (pinfunction "1_1") (pintype "bidirectional"))
    )
    (net (code "62") (name "/GEM_O3_5") (class "Default")
      (node (ref "B4") (pin "1") (pinfunction "1_1") (pintype "bidirectional"))
    )
    (net (code "63") (name "/GEM_O3_6") (class "Default")
      (node (ref "B8") (pin "1") (pinfunction "1_1") (pintype "bidirectional"))
    )
    (net (code "65") (name "/HVQN-E") (class "Default")
      (node (ref "T7") (pin "2") (pinfunction "C_2") (pintype "passive"))
      (node (ref "T7") (pin "4") (pinfunction "C_4") (pintype "passive"))
    )
    (net (code "73") (name "/HVQP-C") (class "Default")
      (node (ref "R110") (pin "2") (pinfunction "2_2") (pintype "passive"))
      (node (ref "R61") (pin "2") (pinfunction "2_2") (pintype "passive"))
    )
    (net (code "75") (name "/HVQP-E") (class "Default")
      (node (ref "T2") (pin "2") (pinfunction "C_2") (pintype "passive"))
      (node (ref "T2") (pin "4") (pinfunction "C_4") (pintype "passive"))
    )
    (net (code "83") (name "/HV_ON") (class "Default")
      (node (ref "T10") (pin "1") (pinfunction "G_1") (pintype "passive"))
    )
    (net (code "84") (name "/HV_OUT") (class "Default")
      (node (ref "R62") (pin "1") (pinfunction "1_1") (pintype "passive"))
      (node (ref "R63") (pin "1") (pinfunction "1_1") (pintype "passive"))
      (node (ref "TP2") (pin "1") (pinfunction "1_1") (pintype "bidirectional"))
    )
    (net (code "85") (name "/Imeas_N") (class "Default")
      (node (ref "D1") (pin "1") (pinfunction "C_1") (pintype "passive"))
      (node (ref "D4") (pin "2") (pinfunction "A_2") (pintype "passive"))
    )
    (net (code "86") (name "/Imeas_P") (class "Default")
      (node (ref "D5") (pin "1") (pinfunction "C_1") (pintype "passive"))
      (node (ref "D6") (pin "2") (pinfunction "A_2") (pintype "passive"))
      (node (ref "R101") (pin "2") (pinfunction "2_2") (pintype "passive"))
      (node (ref "TP5") (pin "1") (pinfunction "1_1") (pintype "bidirectional"))
    )
    (net (code "87") (name "/Interlock") (class "Default")
      (node (ref "D3") (pin "1") (pinfunction "C_1") (pintype "passive"))
      (node (ref "J8") (pin "1") (pinfunction "1_1") (pintype "bidirectional"))
      (node (ref "R29") (pin "1") (pinfunction "1_1") (pintype "passive"))
    )
    (net (code "90") (name "/PG_OUT") (class "Default")
      (node (ref "J9") (pin "1") (pinfunction "1_1") (pintype "bidirectional"))
    )
    (net (code "91") (name "GND") (class "Default")
      (node (ref "D1") (pin "2") (pinfunction "A_2") (pintype "passive"))
      (node (ref "D3") (pin "2") (pinfunction "A_2") (pintype "passive"))
      (node (ref "D4") (pin "1") (pinfunction "C_1") (pintype "passive"))
      (node (ref "D5") (pin "2") (pinfunction "A_2") (pintype "passive"))
      (node (ref "D6") (pin "1") (pinfunction "C_1") (pintype "passive"))
      (node (ref "J8") (pin "2") (pinfunction "2_2") (pintype "bidirectional"))
      (node (ref "J9") (pin "2") (pinfunction "2_2") (pintype "bidirectional"))
      (node (ref "R102") (pin "2") (pinfunction "2_2") (pintype "passive"))
      (node (ref "T10") (pin "2") (pinfunction "S_2") (pintype "passive"))
      (node (ref "T9") (pin "2") (pinfunction "S_2") (pintype "passive"))
    )
    (net (code "92") (name "Net-(P1-CCW)") (class "Default")
      (node (ref "P1") (pin "1") (pinfunction "CCW_1") (pintype "passive"))
      (node (ref "R62") (pin "2") (pinfunction "2_2") (pintype "passive"))
    )
    (net (code "93") (name "Net-(P1-CW)") (class "Default")
      (node (ref "P1") (pin "3") (pinfunction "CW_3") (pintype "passive"))
      (node (ref "R61") (pin "1") (pinfunction "1_1") (pintype "passive"))
    )
    (net (code "94") (name "Net-(P1-W)") (class "Default")
      (node (ref "P1") (pin "2") (pinfunction "W_2") (pintype "passive"))
      (node (ref "T7") (pin "1") (pinfunction "B_1") (pintype "passive"))
    )
    (net (code "95") (name "Net-(P2-Pad1)") (class "Default")
      (node (ref "P2") (pin "1") (pinfunction "1_1") (pintype "passive"))
      (node (ref "P2") (pin "4") (pinfunction "4_4") (pintype "passive"))
      (node (ref "R21") (pin "2") (pinfunction "2_2") (pintype "passive"))
      (node (ref "R24") (pin "1") (pinfunction "1_1") (pintype "passive"))
    )
    (net (code "96") (name "Net-(P2-Pad3)") (class "Default")
      (node (ref "P2") (pin "3") (pinfunction "3_3") (pintype "passive"))
      (node (ref "P2") (pin "6") (pinfunction "6_6") (pintype "passive"))
      (node (ref "R19") (pin "2") (pinfunction "2_2") (pintype "passive"))
      (node (ref "R21") (pin "1") (pinfunction "1_1") (pintype "passive"))
    )
    (net (code "97") (name "Net-(P2-Pad5)") (class "Default")
      (node (ref "P2") (pin "5") (pinfunction "5_5") (pintype "passive"))
      (node (ref "P2") (pin "8") (pinfunction "8_8") (pintype "passive"))
      (node (ref "R17") (pin "2") (pinfunction "2_2") (pintype "passive"))
      (node (ref "R19") (pin "1") (pinfunction "1_1") (pintype "passive"))
    )
    (net (code "98") (name "Net-(P2-Pad7)") (class "Default")
      (node (ref "P2") (pin "7") (pinfunction "7_7") (pintype "passive"))
      (node (ref "R16") (pin "2") (pinfunction "2_2") (pintype "passive"))
      (node (ref "R17") (pin "1") (pinfunction "1_1") (pintype "passive"))
    )
    (net (code "99") (name "Net-(P3-Pad1)") (class "Default")
      (node (ref "P3") (pin "1") (pinfunction "1_1") (pintype "passive"))
      (node (ref "P3") (pin "4") (pinfunction "4_4") (pintype "passive"))
      (node (ref "R33") (pin "2") (pinfunction "2_2") (pintype "passive"))
      (node (ref "R34") (pin "1") (pinfunction "1_1") (pintype "passive"))
    )
    (net (code "100") (name "Net-(P3-Pad3)") (class "Default")
      (node (ref "P3") (pin "3") (pinfunction "3_3") (pintype "passive"))
      (node (ref "P3") (pin "6") (pinfunction "6_6") (pintype "passive"))
      (node (ref "R30") (pin "2") (pinfunction "2_2") (pintype "passive"))
      (node (ref "R33") (pin "1") (pinfunction "1_1") (pintype "passive"))
    )
    (net (code "101") (name "Net-(P3-Pad5)") (class "Default")
      (node (ref "P3") (pin "5") (pinfunction "5_5") (pintype "passive"))
      (node (ref "P3") (pin "8") (pinfunction "8_8") (pintype "passive"))
      (node (ref "R26") (pin "2") (pinfunction "2_2") (pintype "passive"))
      (node (ref "R30") (pin "1") (pinfunction "1_1") (pintype "passive"))
    )
    (net (code "102") (name "Net-(P3-Pad7)") (class "Default")
      (node (ref "P3") (pin "7") (pinfunction "7_7") (pintype "passive"))
      (node (ref "R18") (pin "2") (pinfunction "2_2") (pintype "passive"))
      (node (ref "R26") (pin "1") (pinfunction "1_1") (pintype "passive"))
    )
    (net (code "103") (name "Net-(P4-Pad1)") (class "Default")
      (node (ref "P4") (pin "1") (pinfunction "1_1") (pintype "passive"))
      (node (ref "P4") (pin "4") (pinfunction "4_4") (pintype "passive"))
      (node (ref "R37") (pin "2") (pinfunction "2_2") (pintype "passive"))
      (node (ref "R38") (pin "1") (pinfunction "1_1") (pintype "passive"))
    )
    (net (code "104") (name "Net-(P4-Pad3)") (class "Default")
      (node (ref "P4") (pin "3") (pinfunction "3_3") (pintype "passive"))
      (node (ref "P4") (pin "6") (pinfunction "6_6") (pintype "passive"))
      (node (ref "R36") (pin "2") (pinfunction "2_2") (pintype "passive"))
      (node (ref "R37") (pin "1") (pinfunction "1_1") (pintype "passive"))
    )
    (net (code "105") (name "Net-(P4-Pad5)") (class "Default")
      (node (ref "P4") (pin "5") (pinfunction "5_5") (pintype "passive"))
      (node (ref "P4") (pin "8") (pinfunction "8_8") (pintype "passive"))
      (node (ref "R35") (pin "2") (pinfunction "2_2") (pintype "passive"))
      (node (ref "R36") (pin "1") (pinfunction "1_1") (pintype "passive"))
    )
    (net (code "106") (name "Net-(P4-Pad7)") (class "Default")
      (node (ref "P4") (pin "7") (pinfunction "7_7") (pintype "passive"))
      (node (ref "R20") (pin "2") (pinfunction "2_2") (pintype "passive"))
      (node (ref "R35") (pin "1") (pinfunction "1_1") (pintype "passive"))
    )
    (net (code "107") (name "Net-(P5-Pad1)") (class "Default")
      (node (ref "P5") (pin "1") (pinfunction "1_1") (pintype "passive"))
      (node (ref "P5") (pin "4") (pinfunction "4_4") (pintype "passive"))
      (node (ref "R41") (pin "2") (pinfunction "2_2") (pintype "passive"))
      (node (ref "R42") (pin "1") (pinfunction "1_1") (pintype "passive"))
    )
    (net (code "108") (name "Net-(P5-Pad3)") (class "Default")
      (node (ref "P5") (pin "3") (pinfunction "3_3") (pintype "passive"))
      (node (ref "P5") (pin "6") (pinfunction "6_6") (pintype "passive"))
      (node (ref "R40") (pin "2") (pinfunction "2_2") (pintype "passive"))
      (node (ref "R41") (pin "1") (pinfunction "1_1") (pintype "passive"))
    )
    (net (code "109") (name "Net-(P5-Pad5)") (class "Default")
      (node (ref "P5") (pin "5") (pinfunction "5_5") (pintype "passive"))
      (node (ref "P5") (pin "8") (pinfunction "8_8") (pintype "passive"))
      (node (ref "R39") (pin "2") (pinfunction "2_2") (pintype "passive"))
      (node (ref "R40") (pin "1") (pinfunction "1_1") (pintype "passive"))
    )
    (net (code "110") (name "Net-(P5-Pad7)") (class "Default")
      (node (ref "P5") (pin "7") (pinfunction "7_7") (pintype "passive"))
      (node (ref "R22") (pin "2") (pinfunction "2_2") (pintype "passive"))
      (node (ref "R39") (pin "1") (pinfunction "1_1") (pintype "passive"))
    )
    (net (code "111") (name "Net-(P6-Pad1)") (class "Default")
      (node (ref "P6") (pin "1") (pinfunction "1_1") (pintype "passive"))
      (node (ref "P6") (pin "4") (pinfunction "4_4") (pintype "passive"))
      (node (ref "R57") (pin "2") (pinfunction "2_2") (pintype "passive"))
      (node (ref "R68") (pin "1") (pinfunction "1_1") (pintype "passive"))
    )
    (net (code "112") (name "Net-(P6-Pad3)") (class "Default")
      (node (ref "P6") (pin "3") (pinfunction "3_3") (pintype "passive"))
      (node (ref "P6") (pin "6") (pinfunction "6_6") (pintype "passive"))
      (node (ref "R56") (pin "2") (pinfunction "2_2") (pintype "passive"))
      (node (ref "R57") (pin "1") (pinfunction "1_1") (pintype "passive"))
    )
    (net (code "113") (name "Net-(P6-Pad5)") (class "Default")
      (node (ref "P6") (pin "5") (pinfunction "5_5") (pintype "passive"))
      (node (ref "P6") (pin "8") (pinfunction "8_8") (pintype "passive"))
      (node (ref "R46") (pin "2") (pinfunction "2_2") (pintype "passive"))
      (node (ref "R56") (pin "1") (pinfunction "1_1") (pintype "passive"))
    )
    (net (code "114") (name "Net-(P6-Pad7)") (class "Default")
      (node (ref "P6") (pin "7") (pinfunction "7_7") (pintype "passive"))
      (node (ref "R23") (pin "2") (pinfunction "2_2") (pintype "passive"))
      (node (ref "R46") (pin "1") (pinfunction "1_1") (pintype "passive"))
    )
    (net (code "115") (name "Net-(P7-Pad1)") (class "Default")
      (node (ref "P7") (pin "1") (pinfunction "1_1") (pintype "passive"))
      (node (ref "P7") (pin "4") (pinfunction "4_4") (pintype "passive"))
      (node (ref "R76") (pin "2") (pinfunction "2_2") (pintype "passive"))
      (node (ref "R83") (pin "1") (pinfunction "1_1") (pintype "passive"))
    )
    (net (code "116") (name "Net-(P7-Pad3)") (class "Default")
      (node (ref "P7") (pin "3") (pinfunction "3_3") (pintype "passive"))
      (node (ref "P7") (pin "6") (pinfunction "6_6") (pintype "passive"))
      (node (ref "R75") (pin "2") (pinfunction "2_2") (pintype "passive"))
      (node (ref "R76") (pin "1") (pinfunction "1_1") (pintype "passive"))
    )
    (net (code "117") (name "Net-(P7-Pad5)") (class "Default")
      (node (ref "P7") (pin "5") (pinfunction "5_5") (pintype "passive"))
      (node (ref "P7") (pin "8") (pinfunction "8_8") (pintype "passive"))
      (node (ref "R73") (pin "2") (pinfunction "2_2") (pintype "passive"))
      (node (ref "R75") (pin "1") (pinfunction "1_1") (pintype "passive"))
    )
    (net (code "118") (name "Net-(P7-Pad7)") (class "Default")
      (node (ref "P7") (pin "7") (pinfunction "7_7") (pintype "passive"))
      (node (ref "R25") (pin "2") (pinfunction "2_2") (pintype "passive"))
      (node (ref "R73") (pin "1") (pinfunction "1_1") (pintype "passive"))
    )
    (net (code "119") (name "Net-(P8-CCW)") (class "Default")
      (node (ref "P8") (pin "1") (pinfunction "CCW_1") (pintype "passive"))
      (node (ref "R92") (pin "2") (pinfunction "2_2") (pintype "passive"))
    )
    (net (code "120") (name "Net-(P8-CW)") (class "Default")
      (node (ref "P8") (pin "3") (pinfunction "CW_3") (pintype "passive"))
      (node (ref "R102") (pin "1") (pinfunction "1_1") (pintype "passive"))
    )
    (net (code "121") (name "Net-(P8-W)") (class "Default")
      (node (ref "P8") (pin "2") (pinfunction "W_2") (pintype "passive"))
      (node (ref "T2") (pin "1") (pinfunction "B_1") (pintype "passive"))
    )
    (net (code "122") (name "Net-(P9-Pad1)") (class "Default")
      (node (ref "P9") (pin "1") (pinfunction "1_1") (pintype "passive"))
      (node (ref "P9") (pin "4") (pinfunction "4_4") (pintype "passive"))
      (node (ref "R116") (pin "2") (pinfunction "2_2") (pintype "passive"))
      (node (ref "R117") (pin "1") (pinfunction "1_1") (pintype "passive"))
    )
    (net (code "123") (name "Net-(P9-Pad3)") (class "Default")
      (node (ref "P9") (pin "3") (pinfunction "3_3") (pintype "passive"))
      (node (ref "P9") (pin "6") (pinfunction "6_6") (pintype "passive"))
      (node (ref "R115") (pin "2") (pinfunction "2_2") (pintype "passive"))
      (node (ref "R116") (pin "1") (pinfunction "1_1") (pintype "passive"))
    )
    (net (code "124") (name "Net-(P9-Pad5)") (class "Default")
      (node (ref "P9") (pin "5") (pinfunction "5_5") (pintype "passive"))
      (node (ref "P9") (pin "8") (pinfunction "8_8") (pintype "passive"))
      (node (ref "R114") (pin "2") (pinfunction "2_2") (pintype "passive"))
      (node (ref "R115") (pin "1") (pinfunction "1_1") (pintype "passive"))
    )
    (net (code "125") (name "Net-(P9-Pad7)") (class "Default")
      (node (ref "P9") (pin "7") (pinfunction "7_7") (pintype "passive"))
      (node (ref "R114") (pin "1") (pinfunction "1_1") (pintype "passive"))
      (node (ref "R87") (pin "2") (pinfunction "2_2") (pintype "passive"))
    )
    (net (code "126") (name "Net-(R87-Pad1)") (class "Default")
      (node (ref "R87") (pin "1") (pinfunction "1_1") (pintype "passive"))
      (node (ref "R91") (pin "2") (pinfunction "2_2") (pintype "passive"))
    )
    (net (code "127") (name "Net-(T2-E)") (class "Default")
      (node (ref "R101") (pin "1") (pinfunction "1_1") (pintype "passive"))
      (node (ref "T2") (pin "3") (pinfunction "E_3") (pintype "passive"))
      (node (ref "TP4") (pin "1") (pinfunction "1_1") (pintype "bidirectional"))
    )
    (net (code "128") (name "Net-(T7-E)") (class "Default")
      (node (ref "R63") (pin "2") (pinfunction "2_2") (pintype "passive"))
      (node (ref "T7") (pin "3") (pinfunction "E_3") (pintype "passive"))
      (node (ref "TP1") (pin "1") (pinfunction "1_1") (pintype "bidirectional"))
    )
    (net (code "129") (name "Net-(T9-D)") (class "Default")
      (node (ref "R119") (pin "1") (pinfunction "1_1") (pintype "passive"))
      (node (ref "T9") (pin "3") (pinfunction "D_3") (pintype "passive"))
    )
    (net (code "130") (name "Net-(T10-D)") (class "Default")
      (node (ref "R120") (pin "1") (pinfunction "1_1") (pintype "passive"))
      (node (ref "T10") (pin "3") (pinfunction "D_3") (pintype "passive"))
      (node (ref "T9") (pin "1") (pinfunction "G_1") (pintype "passive"))
    )
    (net (code "131") (name "P3V3") (class "Default")
      (node (ref "R29") (pin "2") (pinfunction "2_2") (pintype "passive"))
    )
    (net (code "132") (name "P5V0") (class "Default")
      (node (ref "R120") (pin "2") (pinfunction "2_2") (pintype "passive"))
    )
  )
)
